# CurrentSense.net
KiCad netlist of a schematic drawn in Altium Designer
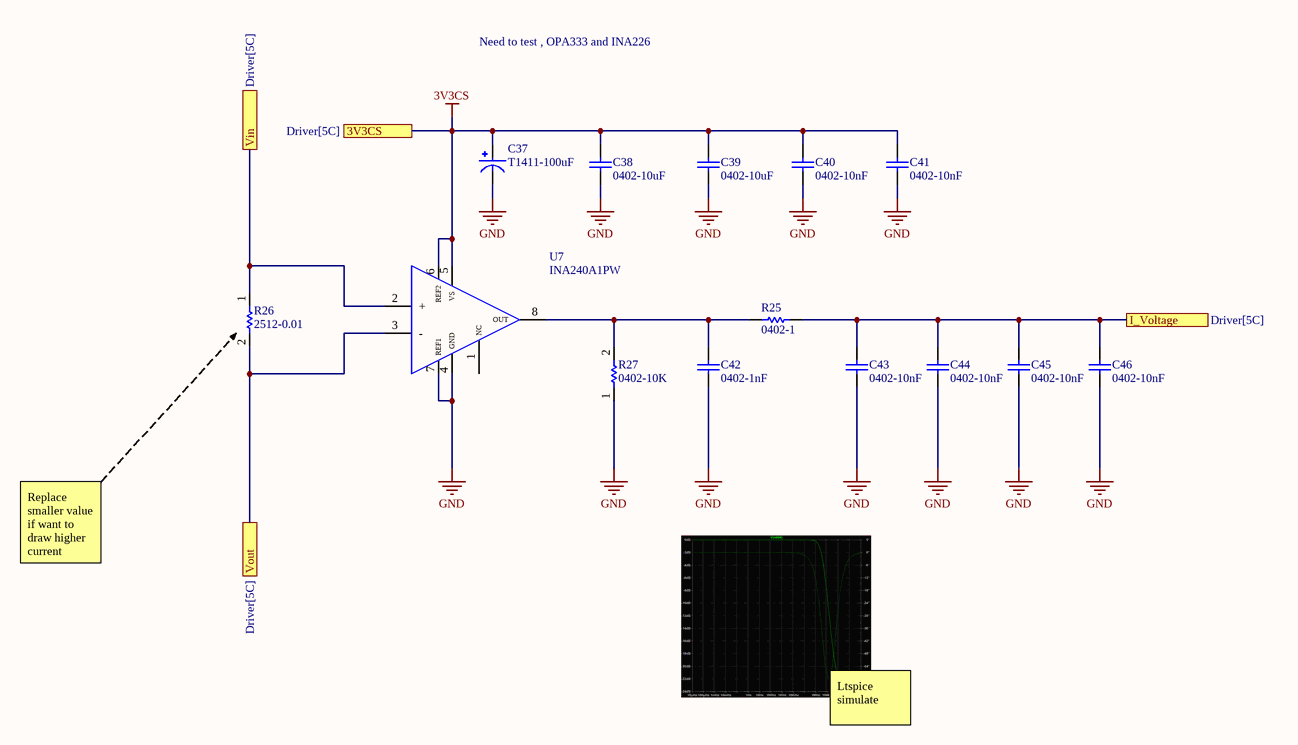
[diagram p0: CurrentSense.SchDoc]

(export (version "E")
  (design (tool "Eeschema 10.0.6"))
  (components
    (comp (ref "C37")
      (value "T1411-100uF")
      (footprint "CAPPC3528X210N")
      (description "100µF Molded Tantalum Polymer Capacitor 25 V 1411 (3528 Metric), 1210 150mOhm @ 100kHz")
      (fields (field (name "MF") "AVX") (field (name "MP") "TCJB106M025R0150"))
      (libsource (lib "Tin Tran") (part "T1411-100uF"))
    )
    (comp (ref "C38")
      (value "0402-10uF")
      (footprint "CAPC0402(1005)60_N")
      (description "Capacitor 10uF 0402s")
      (fields (field (name "TOLERANCE") "20%"))
      (libsource (lib "Tin Tran") (part "0402"))
    )
    (comp (ref "C39")
      (value "0402-10uF")
      (footprint "CAPC0402(1005)60_N")
      (description "Capacitor 10uF 0402s")
      (fields (field (name "TOLERANCE") "20%"))
      (libsource (lib "Tin Tran") (part "0402"))
    )
    (comp (ref "C40")
      (value "0402-10nF")
      (footprint "CAPC0402(1005)60_N")
      (description "Capacitor 10nF 0402")
      (fields (field (name "TOLERANCE") "20%"))
      (libsource (lib "Tin Tran") (part "0402"))
    )
    (comp (ref "C41")
      (value "0402-10nF")
      (footprint "CAPC0402(1005)60_N")
      (description "Capacitor 10nF 0402")
      (fields (field (name "TOLERANCE") "20%"))
      (libsource (lib "Tin Tran") (part "0402"))
    )
    (comp (ref "C42")
      (value "0402-1nF")
      (footprint "CAPC0402(1005)60_N")
      (description "Capacitor 1nF 0402")
      (fields (field (name "TOLERANCE") "20%"))
      (libsource (lib "Tin Tran") (part "0402"))
    )
    (comp (ref "C43")
      (value "0402-10nF")
      (footprint "CAPC0402(1005)60_N")
      (description "Capacitor 10nF 0402")
      (fields (field (name "TOLERANCE") "20%"))
      (libsource (lib "Tin Tran") (part "0402"))
    )
    (comp (ref "C44")
      (value "0402-10nF")
      (footprint "CAPC0402(1005)60_N")
      (description "Capacitor 10nF 0402")
      (fields (field (name "TOLERANCE") "20%"))
      (libsource (lib "Tin Tran") (part "0402"))
    )
    (comp (ref "C45")
      (value "0402-10nF")
      (footprint "CAPC0402(1005)60_N")
      (description "Capacitor 10nF 0402")
      (fields (field (name "TOLERANCE") "20%"))
      (libsource (lib "Tin Tran") (part "0402"))
    )
    (comp (ref "C46")
      (value "0402-10nF")
      (footprint "CAPC0402(1005)60_N")
      (description "Capacitor 10nF 0402")
      (fields (field (name "TOLERANCE") "20%"))
      (libsource (lib "Tin Tran") (part "0402"))
    )
    (comp (ref "R25")
      (value "0402-1")
      (footprint "R-0402-1K")
      (description "0402Resistor 1Ohm")
      (libsource (lib "") (part "0402_2"))
    )
    (comp (ref "R26")
      (value "2512-0.01")
      (footprint "FP-WSLP2512R0100FEA-IPC_A")
      (description "RES 0.01 OHM 1% 3W 2512")
      (fields (field (name "TOLERANCE") "1%"))
      (libsource (lib "Tin Tran") (part "2512"))
    )
    (comp (ref "R27")
      (value "0402-10K")
      (footprint "R-0402-10K")
      (description "RES 0402 10K")
      (libsource (lib "") (part "0402_1"))
    )
    (comp (ref "U7")
      (value "INA240A1PW")
      (footprint "SOP65P640X120-8N")
      (description "-4 to 80V, bidirectional, ultra-precise current sense amplifier with enhanced PWM rejection")
      (fields (field (name "MF") "Texas Instruments"))
      (libsource (lib "Tin Tran") (part "INA240A1PW"))
    )
  )
  (nets
    (net (code "1") (name "/I_Voltage") (class "Default")
      (node (ref "C43") (pin "2") (pinfunction "2_2") (pintype "passive"))
      (node (ref "C44") (pin "2") (pinfunction "2_2") (pintype "passive"))
      (node (ref "C45") (pin "2") (pinfunction "2_2") (pintype "passive"))
      (node (ref "C46") (pin "2") (pinfunction "2_2") (pintype "passive"))
      (node (ref "R25") (pin "2") (pinfunction "2_2") (pintype "passive"))
    )
    (net (code "2") (name "/Vin") (class "Default")
      (node (ref "R26") (pin "1") (pinfunction "1_1") (pintype "passive"))
      (node (ref "U7") (pin "2") (pinfunction "+_2") (pintype "passive"))
    )
    (net (code "3") (name "/Vout") (class "Default")
      (node (ref "R26") (pin "2") (pinfunction "2_2") (pintype "passive"))
      (node (ref "U7") (pin "3") (pinfunction "-_3") (pintype "passive"))
    )
    (net (code "4") (name "3V3CS") (class "Default")
      (node (ref "C37") (pin "1") (pinfunction "1_1") (pintype "passive"))
      (node (ref "C38") (pin "2") (pinfunction "2_2") (pintype "passive"))
      (node (ref "C39") (pin "2") (pinfunction "2_2") (pintype "passive"))
      (node (ref "C40") (pin "2") (pinfunction "2_2") (pintype "passive"))
      (node (ref "C41") (pin "2") (pinfunction "2_2") (pintype "passive"))
      (node (ref "U7") (pin "5") (pinfunction "VS_5") (pintype "passive"))
      (node (ref "U7") (pin "6") (pinfunction "REF2_6") (pintype "passive"))
    )
    (net (code "5") (name "GND") (class "Default")
      (node (ref "C37") (pin "2") (pinfunction "2_2") (pintype "passive"))
      (node (ref "C38") (pin "1") (pinfunction "1_1") (pintype "passive"))
      (node (ref "C39") (pin "1") (pinfunction "1_1") (pintype "passive"))
      (node (ref "C40") (pin "1") (pinfunction "1_1") (pintype "passive"))
      (node (ref "C41") (pin "1") (pinfunction "1_1") (pintype "passive"))
      (node (ref "C42") (pin "1") (pinfunction "1_1") (pintype "passive"))
      (node (ref "C43") (pin "1") (pinfunction "1_1") (pintype "passive"))
      (node (ref "C44") (pin "1") (pinfunction "1_1") (pintype "passive"))
      (node (ref "C45") (pin "1") (pinfunction "1_1") (pintype "passive"))
      (node (ref "C46") (pin "1") (pinfunction "1_1") (pintype "passive"))
      (node (ref "R27") (pin "1") (pinfunction "1_1") (pintype "passive"))
      (node (ref "U7") (pin "4") (pinfunction "GND_4") (pintype "passive"))
      (node (ref "U7") (pin "7") (pinfunction "REF1_7") (pintype "passive"))
    )
    (net (code "6") (name "Net-(U7-OUT)") (class "Default")
      (node (ref "C42") (pin "2") (pinfunction "2_2") (pintype "passive"))
      (node (ref "R25") (pin "1") (pinfunction "1_1") (pintype "passive"))
      (node (ref "R27") (pin "2") (pinfunction "2_2") (pintype "passive"))
      (node (ref "U7") (pin "8") (pinfunction "OUT_8") (pintype "passive"))
    )
    (net (code "7") (name "unconnected-(U7-NC-Pad1)") (class "Default")
      (node (ref "U7") (pin "1") (pinfunction "NC_1") (pintype "passive"))
    )
  )
)
